# STM32.net
KiCad netlist of a schematic drawn in Altium Designer
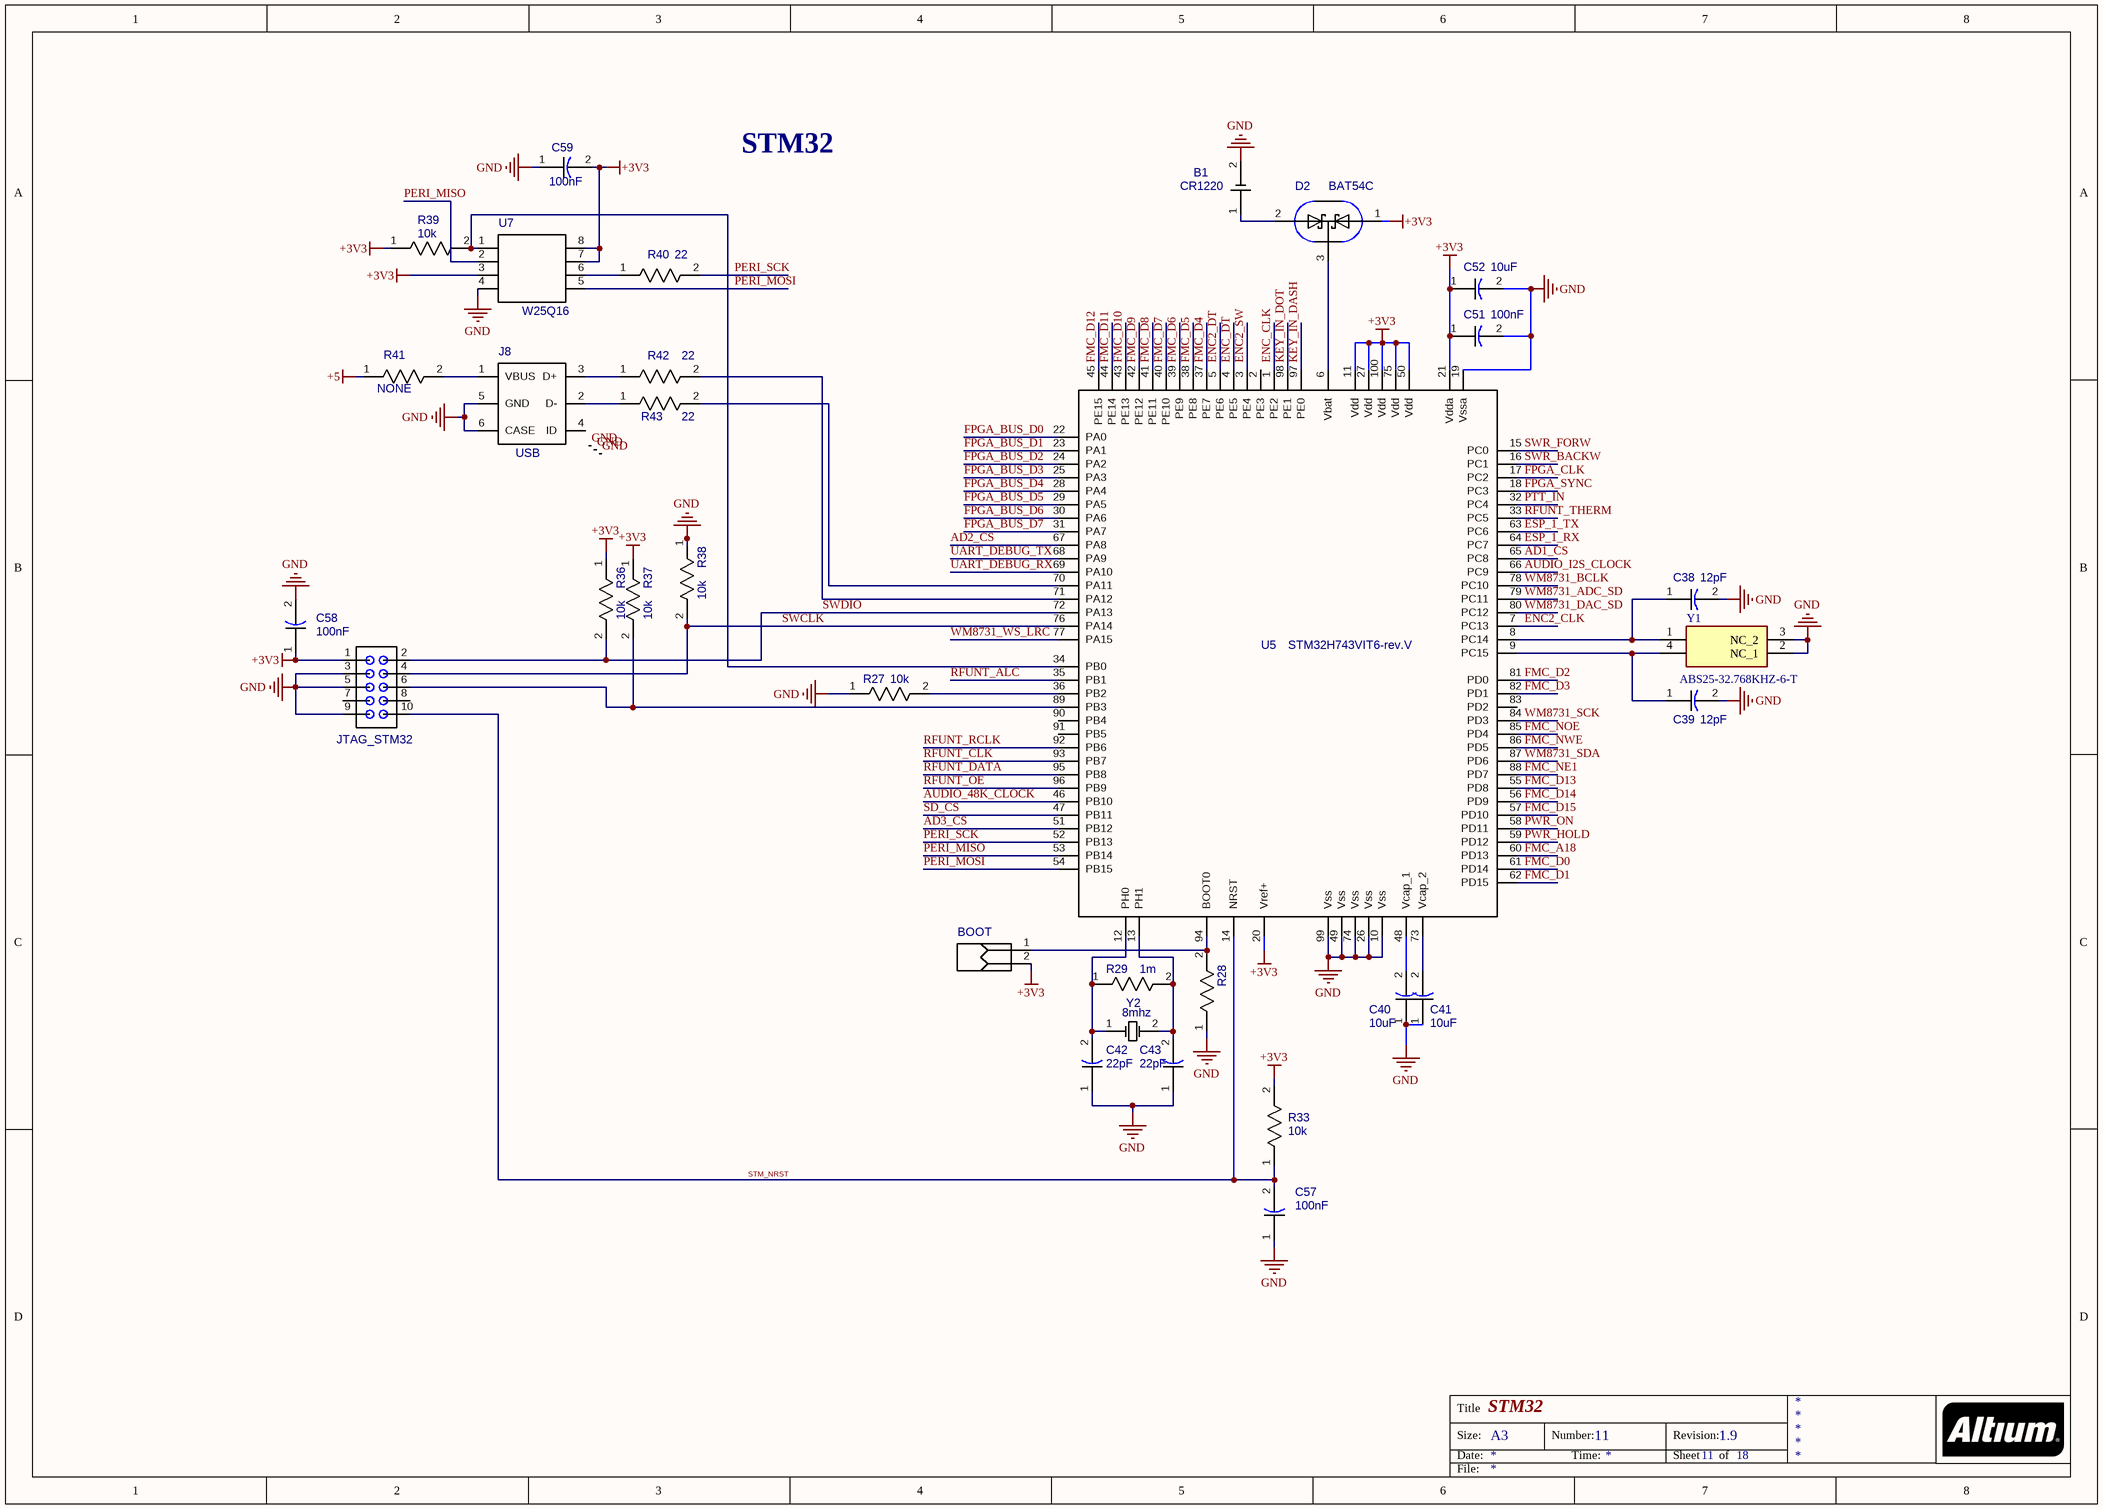
[diagram p0: STM32.SchDoc]

(export (version "E")
  (design (tool "Eeschema 10.0.6"))
  (components
    (comp (ref "B1")
      (value "CR1220")
      (footprint "BR1632A/FA")
      (description "BR1632A/FA")
      (libsource (lib "*") (part "BR1632A/FA"))
    )
    (comp (ref "BOOT")
      (value "~")
      (footprint "51022-0200")
      (description "2 Pin")
      (libsource (lib "*") (part "51022-0200"))
    )
    (comp (ref "C38")
      (value "12pF")
      (footprint "CAP_0805")
      (description "CAP_0805")
      (libsource (lib "*") (part "CAP_0805"))
    )
    (comp (ref "C39")
      (value "12pF")
      (footprint "CAP_0805")
      (description "CAP_0805")
      (libsource (lib "*") (part "CAP_0805"))
    )
    (comp (ref "C40")
      (value "10uF")
      (footprint "CAP_0805")
      (description "CAP_0805")
      (libsource (lib "*") (part "CAP_0805"))
    )
    (comp (ref "C41")
      (value "10uF")
      (footprint "CAP_0805")
      (description "CAP_0805")
      (libsource (lib "*") (part "CAP_0805"))
    )
    (comp (ref "C42")
      (value "22pF")
      (footprint "CAP_0805")
      (description "CAP_0805")
      (libsource (lib "*") (part "CAP_0805"))
    )
    (comp (ref "C43")
      (value "22pF")
      (footprint "CAP_0805")
      (description "CAP_0805")
      (libsource (lib "*") (part "CAP_0805"))
    )
    (comp (ref "C51")
      (value "100nF")
      (footprint "CAP_0805")
      (description "CAP_0805")
      (libsource (lib "*") (part "CAP_0805"))
    )
    (comp (ref "C52")
      (value "10uF")
      (footprint "CAP_0805")
      (description "CAP_0805")
      (libsource (lib "*") (part "CAP_0805"))
    )
    (comp (ref "C57")
      (value "100nF")
      (footprint "CAP_0805")
      (description "CAP_0805")
      (libsource (lib "*") (part "CAP_0805"))
    )
    (comp (ref "C58")
      (value "100nF")
      (footprint "CAP_0805")
      (description "CAP_0805")
      (libsource (lib "*") (part "CAP_0805"))
    )
    (comp (ref "C59")
      (value "100nF")
      (footprint "CAP_0805")
      (description "CAP_0805")
      (libsource (lib "*") (part "CAP_0805"))
    )
    (comp (ref "D2") (value "BAT54C") (footprint "BAT54C") (libsource (lib "*") (part "BAT54C")))
    (comp (ref "J8")
      (value "USB")
      (footprint "2-1734035-3")
      (description "2-1734035-3")
      (libsource (lib "*") (part "2-1734035-3"))
    )
    (comp (ref "JTAG_STM32")
      (value "~")
      (footprint "IDC10")
      (description "2*5 Pin")
      (libsource (lib "*") (part "IDC10"))
    )
    (comp (ref "R27")
      (value "10k")
      (footprint "RES_0805")
      (description "RES_0805")
      (libsource (lib "*") (part "RES_0805"))
    )
    (comp (ref "R28")
      (value "10k")
      (footprint "RES_0805")
      (description "RES_0805")
      (libsource (lib "*") (part "RES_0805"))
    )
    (comp (ref "R29")
      (value "1m")
      (footprint "RES_0805")
      (description "RES_0805")
      (libsource (lib "*") (part "RES_0805"))
    )
    (comp (ref "R33")
      (value "10k")
      (footprint "RES_0805")
      (description "RES_0805")
      (libsource (lib "*") (part "RES_0805"))
    )
    (comp (ref "R36")
      (value "10k")
      (footprint "RES_0805")
      (description "RES_0805")
      (libsource (lib "*") (part "RES_0805"))
    )
    (comp (ref "R37")
      (value "10k")
      (footprint "RES_0805")
      (description "RES_0805")
      (libsource (lib "*") (part "RES_0805"))
    )
    (comp (ref "R38")
      (value "10k")
      (footprint "RES_0805")
      (description "RES_0805")
      (libsource (lib "*") (part "RES_0805"))
    )
    (comp (ref "R39")
      (value "10k")
      (footprint "RES_0805")
      (description "RES_0805")
      (libsource (lib "*") (part "RES_0805"))
    )
    (comp (ref "R40")
      (value "22")
      (footprint "RES_0805")
      (description "RES_0805")
      (libsource (lib "*") (part "RES_0805"))
    )
    (comp (ref "R41")
      (value "NONE")
      (footprint "RES_0805")
      (description "RES_0805")
      (libsource (lib "*") (part "RES_0805"))
    )
    (comp (ref "R42")
      (value "22")
      (footprint "RES_0805")
      (description "RES_0805")
      (libsource (lib "*") (part "RES_0805"))
    )
    (comp (ref "R43")
      (value "22")
      (footprint "RES_0805")
      (description "RES_0805")
      (libsource (lib "*") (part "RES_0805"))
    )
    (comp (ref "U5")
      (value "STM32H743VIT6-rev.V")
      (footprint "STM32H743VIT6")
      (description "STM32H743VIT6")
      (libsource (lib "*") (part "STM32H743VIT6"))
    )
    (comp (ref "U7") (value "W25Q16") (footprint "W25Q16") (libsource (lib "*") (part "W25Q16")))
    (comp (ref "Y1")
      (value "ABS25-32.768KHZ-6-T")
      (footprint "SamacSys:ABS25")
      (description "Crystal or Oscillator")
      (fields
        (field (name "MOUSER PART NUMBER") "815-ABS25-32.768K6-T")
        (field (name "RS PART NUMBER") "1712795P")
      )
      (libsource (lib "*") (part "ABS25-32.768KHZ-6-T"))
    )
    (comp (ref "Y2")
      (value "8mhz")
      (footprint "ECS-200-20-1")
      (description "ECS-200-20-1")
      (libsource (lib "*") (part "ECS-200-20-1"))
    )
  )
  (nets
    (net (code "1") (name "+3V3") (class "Default")
      (node (ref "BOOT") (pin "2") (pinfunction "2_2") (pintype "passive"))
      (node (ref "C51") (pin "1") (pinfunction "1_1") (pintype "passive"))
      (node (ref "C52") (pin "1") (pinfunction "1_1") (pintype "passive"))
      (node (ref "C58") (pin "1") (pinfunction "1_1") (pintype "passive"))
      (node (ref "C59") (pin "2") (pinfunction "2_2") (pintype "passive"))
      (node (ref "D2") (pin "1") (pinfunction "(A1)_1") (pintype "passive"))
      (node (ref "JTAG_STM32") (pin "1") (pinfunction "1_1") (pintype "passive"))
      (node (ref "R33") (pin "2") (pinfunction "2_2") (pintype "passive"))
      (node (ref "R36") (pin "1") (pinfunction "1_1") (pintype "passive"))
      (node (ref "R37") (pin "1") (pinfunction "1_1") (pintype "passive"))
      (node (ref "R39") (pin "1") (pinfunction "1_1") (pintype "passive"))
      (node (ref "U5") (pin "100") (pinfunction "Vdd_100") (pintype "passive"))
      (node (ref "U5") (pin "11") (pinfunction "Vdd_11") (pintype "passive"))
      (node (ref "U5") (pin "20") (pinfunction "Vref+_20") (pintype "passive"))
      (node (ref "U5") (pin "21") (pinfunction "Vdda_21") (pintype "passive"))
      (node (ref "U5") (pin "27") (pinfunction "Vdd_27") (pintype "passive"))
      (node (ref "U5") (pin "50") (pinfunction "Vdd_50") (pintype "passive"))
      (node (ref "U5") (pin "75") (pinfunction "Vdd_75") (pintype "passive"))
      (node (ref "U7") (pin "3") (pinfunction "WP_3") (pintype "passive"))
      (node (ref "U7") (pin "7") (pinfunction "HOLD_7") (pintype "passive"))
      (node (ref "U7") (pin "8") (pinfunction "VCC_8") (pintype "passive"))
    )
    (net (code "2") (name "+5") (class "Default")
      (node (ref "R41") (pin "1") (pinfunction "1_1") (pintype "passive"))
    )
    (net (code "3") (name "/AD1_CS") (class "Default")
      (node (ref "U5") (pin "65") (pinfunction "PC8_65") (pintype "passive"))
    )
    (net (code "4") (name "/AD2_CS") (class "Default")
      (node (ref "U5") (pin "67") (pinfunction "PA8_67") (pintype "passive"))
    )
    (net (code "5") (name "/AD3_CS") (class "Default")
      (node (ref "U5") (pin "51") (pinfunction "PB12_51") (pintype "passive"))
    )
    (net (code "6") (name "/AUDIO_48K_CLOCK") (class "Default")
      (node (ref "U5") (pin "46") (pinfunction "PB10_46") (pintype "passive"))
    )
    (net (code "7") (name "/AUDIO_I2S_CLOCK") (class "Default")
      (node (ref "U5") (pin "66") (pinfunction "PC9_66") (pintype "passive"))
    )
    (net (code "8") (name "/ENC2_CLK") (class "Default")
      (node (ref "U5") (pin "7") (pinfunction "PC13_7") (pintype "passive"))
    )
    (net (code "9") (name "/ENC2_DT") (class "Default")
      (node (ref "U5") (pin "5") (pinfunction "PE6_5") (pintype "passive"))
    )
    (net (code "10") (name "/ENC2_SW") (class "Default")
      (node (ref "U5") (pin "3") (pinfunction "PE4_3") (pintype "passive"))
    )
    (net (code "11") (name "/ENC_CLK") (class "Default")
      (node (ref "U5") (pin "1") (pinfunction "PE2_1") (pintype "passive"))
    )
    (net (code "12") (name "/ENC_DT") (class "Default")
      (node (ref "U5") (pin "4") (pinfunction "PE5_4") (pintype "passive"))
    )
    (net (code "13") (name "/ESP_1_RX") (class "Default")
      (node (ref "U5") (pin "64") (pinfunction "PC7_64") (pintype "passive"))
    )
    (net (code "14") (name "/ESP_1_TX") (class "Default")
      (node (ref "U5") (pin "63") (pinfunction "PC6_63") (pintype "passive"))
    )
    (net (code "15") (name "/FMC_A18") (class "Default")
      (node (ref "U5") (pin "60") (pinfunction "PD13_60") (pintype "passive"))
    )
    (net (code "16") (name "/FMC_D0") (class "Default")
      (node (ref "U5") (pin "61") (pinfunction "PD14_61") (pintype "passive"))
    )
    (net (code "17") (name "/FMC_D1") (class "Default")
      (node (ref "U5") (pin "62") (pinfunction "PD15_62") (pintype "passive"))
    )
    (net (code "18") (name "/FMC_D2") (class "Default")
      (node (ref "U5") (pin "81") (pinfunction "PD0_81") (pintype "passive"))
    )
    (net (code "19") (name "/FMC_D3") (class "Default")
      (node (ref "U5") (pin "82") (pinfunction "PD1_82") (pintype "passive"))
    )
    (net (code "20") (name "/FMC_D4") (class "Default")
      (node (ref "U5") (pin "37") (pinfunction "PE7_37") (pintype "passive"))
    )
    (net (code "21") (name "/FMC_D5") (class "Default")
      (node (ref "U5") (pin "38") (pinfunction "PE8_38") (pintype "passive"))
    )
    (net (code "22") (name "/FMC_D6") (class "Default")
      (node (ref "U5") (pin "39") (pinfunction "PE9_39") (pintype "passive"))
    )
    (net (code "23") (name "/FMC_D7") (class "Default")
      (node (ref "U5") (pin "40") (pinfunction "PE10_40") (pintype "passive"))
    )
    (net (code "24") (name "/FMC_D8") (class "Default")
      (node (ref "U5") (pin "41") (pinfunction "PE11_41") (pintype "passive"))
    )
    (net (code "25") (name "/FMC_D9") (class "Default")
      (node (ref "U5") (pin "42") (pinfunction "PE12_42") (pintype "passive"))
    )
    (net (code "26") (name "/FMC_D10") (class "Default")
      (node (ref "U5") (pin "43") (pinfunction "PE13_43") (pintype "passive"))
    )
    (net (code "27") (name "/FMC_D11") (class "Default")
      (node (ref "U5") (pin "44") (pinfunction "PE14_44") (pintype "passive"))
    )
    (net (code "28") (name "/FMC_D12") (class "Default")
      (node (ref "U5") (pin "45") (pinfunction "PE15_45") (pintype "passive"))
    )
    (net (code "29") (name "/FMC_D13") (class "Default")
      (node (ref "U5") (pin "55") (pinfunction "PD8_55") (pintype "passive"))
    )
    (net (code "30") (name "/FMC_D14") (class "Default")
      (node (ref "U5") (pin "56") (pinfunction "PD9_56") (pintype "passive"))
    )
    (net (code "31") (name "/FMC_D15") (class "Default")
      (node (ref "U5") (pin "57") (pinfunction "PD10_57") (pintype "passive"))
    )
    (net (code "32") (name "/FMC_NE1") (class "Default")
      (node (ref "U5") (pin "88") (pinfunction "PD7_88") (pintype "passive"))
    )
    (net (code "33") (name "/FMC_NOE") (class "Default")
      (node (ref "U5") (pin "85") (pinfunction "PD4_85") (pintype "passive"))
    )
    (net (code "34") (name "/FMC_NWE") (class "Default")
      (node (ref "U5") (pin "86") (pinfunction "PD5_86") (pintype "passive"))
    )
    (net (code "35") (name "/FPGA_BUS_D0") (class "Default")
      (node (ref "U5") (pin "22") (pinfunction "PA0_22") (pintype "passive"))
    )
    (net (code "36") (name "/FPGA_BUS_D1") (class "Default")
      (node (ref "U5") (pin "23") (pinfunction "PA1_23") (pintype "passive"))
    )
    (net (code "37") (name "/FPGA_BUS_D2") (class "Default")
      (node (ref "U5") (pin "24") (pinfunction "PA2_24") (pintype "passive"))
    )
    (net (code "38") (name "/FPGA_BUS_D3") (class "Default")
      (node (ref "U5") (pin "25") (pinfunction "PA3_25") (pintype "passive"))
    )
    (net (code "39") (name "/FPGA_BUS_D4") (class "Default")
      (node (ref "U5") (pin "28") (pinfunction "PA4_28") (pintype "passive"))
    )
    (net (code "40") (name "/FPGA_BUS_D5") (class "Default")
      (node (ref "U5") (pin "29") (pinfunction "PA5_29") (pintype "passive"))
    )
    (net (code "41") (name "/FPGA_BUS_D6") (class "Default")
      (node (ref "U5") (pin "30") (pinfunction "PA6_30") (pintype "passive"))
    )
    (net (code "42") (name "/FPGA_BUS_D7") (class "Default")
      (node (ref "U5") (pin "31") (pinfunction "PA7_31") (pintype "passive"))
    )
    (net (code "43") (name "/FPGA_CLK") (class "Default")
      (node (ref "U5") (pin "17") (pinfunction "PC2_17") (pintype "passive"))
    )
    (net (code "44") (name "/FPGA_SYNC") (class "Default")
      (node (ref "U5") (pin "18") (pinfunction "PC3_18") (pintype "passive"))
    )
    (net (code "45") (name "/KEY_IN_DASH") (class "Default")
      (node (ref "U5") (pin "97") (pinfunction "PE0_97") (pintype "passive"))
    )
    (net (code "46") (name "/KEY_IN_DOT") (class "Default")
      (node (ref "U5") (pin "98") (pinfunction "PE1_98") (pintype "passive"))
    )
    (net (code "47") (name "/PERI_MISO") (class "Default")
      (node (ref "U5") (pin "53") (pinfunction "PB14_53") (pintype "passive"))
      (node (ref "U7") (pin "2") (pinfunction "SO_2") (pintype "passive"))
    )
    (net (code "48") (name "/PERI_MOSI") (class "Default")
      (node (ref "U5") (pin "54") (pinfunction "PB15_54") (pintype "passive"))
      (node (ref "U7") (pin "5") (pinfunction "SI_5") (pintype "passive"))
    )
    (net (code "49") (name "/PERI_SCK") (class "Default")
      (node (ref "R40") (pin "2") (pinfunction "2_2") (pintype "passive"))
      (node (ref "U5") (pin "52") (pinfunction "PB13_52") (pintype "passive"))
    )
    (net (code "50") (name "/PTT_IN") (class "Default")
      (node (ref "U5") (pin "32") (pinfunction "PC4_32") (pintype "passive"))
    )
    (net (code "51") (name "/PWR_HOLD") (class "Default")
      (node (ref "U5") (pin "59") (pinfunction "PD12_59") (pintype "passive"))
    )
    (net (code "52") (name "/PWR_ON") (class "Default")
      (node (ref "U5") (pin "58") (pinfunction "PD11_58") (pintype "passive"))
    )
    (net (code "53") (name "/RFUNT_ALC") (class "Default")
      (node (ref "U5") (pin "35") (pinfunction "PB1_35") (pintype "passive"))
    )
    (net (code "54") (name "/RFUNT_CLK") (class "Default")
      (node (ref "U5") (pin "93") (pinfunction "PB7_93") (pintype "passive"))
    )
    (net (code "55") (name "/RFUNT_DATA") (class "Default")
      (node (ref "U5") (pin "95") (pinfunction "PB8_95") (pintype "passive"))
    )
    (net (code "56") (name "/RFUNT_OE") (class "Default")
      (node (ref "U5") (pin "96") (pinfunction "PB9_96") (pintype "passive"))
    )
    (net (code "57") (name "/RFUNT_RCLK") (class "Default")
      (node (ref "U5") (pin "92") (pinfunction "PB6_92") (pintype "passive"))
    )
    (net (code "58") (name "/RFUNT_THERM") (class "Default")
      (node (ref "U5") (pin "33") (pinfunction "PC5_33") (pintype "passive"))
    )
    (net (code "59") (name "/SD_CS") (class "Default")
      (node (ref "U5") (pin "47") (pinfunction "PB11_47") (pintype "passive"))
    )
    (net (code "60") (name "/STM_NRST") (class "Default")
      (node (ref "C57") (pin "2") (pinfunction "2_2") (pintype "passive"))
      (node (ref "JTAG_STM32") (pin "10") (pinfunction "10_10") (pintype "passive"))
      (node (ref "R33") (pin "1") (pinfunction "1_1") (pintype "passive"))
      (node (ref "U5") (pin "14") (pinfunction "NRST_14") (pintype "passive"))
    )
    (net (code "61") (name "/SWCLK") (class "Default")
      (node (ref "JTAG_STM32") (pin "4") (pinfunction "4_4") (pintype "passive"))
      (node (ref "R38") (pin "2") (pinfunction "2_2") (pintype "passive"))
      (node (ref "U5") (pin "76") (pinfunction "PA14_76") (pintype "passive"))
    )
    (net (code "62") (name "/SWDIO") (class "Default")
      (node (ref "JTAG_STM32") (pin "2") (pinfunction "2_2") (pintype "passive"))
      (node (ref "R36") (pin "2") (pinfunction "2_2") (pintype "passive"))
      (node (ref "U5") (pin "72") (pinfunction "PA13_72") (pintype "passive"))
    )
    (net (code "63") (name "/SWR_BACKW") (class "Default")
      (node (ref "U5") (pin "16") (pinfunction "PC1_16") (pintype "passive"))
    )
    (net (code "64") (name "/SWR_FORW") (class "Default")
      (node (ref "U5") (pin "15") (pinfunction "PC0_15") (pintype "passive"))
    )
    (net (code "65") (name "/UART_DEBUG_RX") (class "Default")
      (node (ref "U5") (pin "69") (pinfunction "PA10_69") (pintype "passive"))
    )
    (net (code "66") (name "/UART_DEBUG_TX") (class "Default")
      (node (ref "U5") (pin "68") (pinfunction "PA9_68") (pintype "passive"))
    )
    (net (code "67") (name "/WM8731_ADC_SD") (class "Default")
      (node (ref "U5") (pin "79") (pinfunction "PC11_79") (pintype "passive"))
    )
    (net (code "68") (name "/WM8731_BCLK") (class "Default")
      (node (ref "U5") (pin "78") (pinfunction "PC10_78") (pintype "passive"))
    )
    (net (code "69") (name "/WM8731_DAC_SD") (class "Default")
      (node (ref "U5") (pin "80") (pinfunction "PC12_80") (pintype "passive"))
    )
    (net (code "70") (name "/WM8731_SCK") (class "Default")
      (node (ref "U5") (pin "84") (pinfunction "PD3_84") (pintype "passive"))
    )
    (net (code "71") (name "/WM8731_SDA") (class "Default")
      (node (ref "U5") (pin "87") (pinfunction "PD6_87") (pintype "passive"))
    )
    (net (code "72") (name "/WM8731_WS_LRC") (class "Default")
      (node (ref "U5") (pin "77") (pinfunction "PA15_77") (pintype "passive"))
    )
    (net (code "73") (name "GND") (class "Default")
      (node (ref "B1") (pin "2") (pinfunction "NEG_2") (pintype "passive"))
      (node (ref "C38") (pin "2") (pinfunction "2_2") (pintype "passive"))
      (node (ref "C39") (pin "2") (pinfunction "2_2") (pintype "passive"))
      (node (ref "C40") (pin "1") (pinfunction "1_1") (pintype "passive"))
      (node (ref "C41") (pin "1") (pinfunction "1_1") (pintype "passive"))
      (node (ref "C42") (pin "1") (pinfunction "1_1") (pintype "passive"))
      (node (ref "C43") (pin "1") (pinfunction "1_1") (pintype "passive"))
      (node (ref "C51") (pin "2") (pinfunction "2_2") (pintype "passive"))
      (node (ref "C52") (pin "2") (pinfunction "2_2") (pintype "passive"))
      (node (ref "C57") (pin "1") (pinfunction "1_1") (pintype "passive"))
      (node (ref "C58") (pin "2") (pinfunction "2_2") (pintype "passive"))
      (node (ref "C59") (pin "1") (pinfunction "1_1") (pintype "passive"))
      (node (ref "J8") (pin "5") (pinfunction "GND_5") (pintype "passive"))
      (node (ref "J8") (pin "6") (pinfunction "CASE_6") (pintype "passive"))
      (node (ref "J8") (pin "7") (pinfunction "0_7") (pintype "passive"))
      (node (ref "J8") (pin "8") (pinfunction "0_8") (pintype "passive"))
      (node (ref "J8") (pin "9") (pinfunction "0_9") (pintype "passive"))
      (node (ref "JTAG_STM32") (pin "3") (pinfunction "3_3") (pintype "passive"))
      (node (ref "JTAG_STM32") (pin "5") (pinfunction "5_5") (pintype "passive"))
      (node (ref "JTAG_STM32") (pin "9") (pinfunction "9_9") (pintype "passive"))
      (node (ref "R27") (pin "1") (pinfunction "1_1") (pintype "passive"))
      (node (ref "R28") (pin "1") (pinfunction "1_1") (pintype "passive"))
      (node (ref "R38") (pin "1") (pinfunction "1_1") (pintype "passive"))
      (node (ref "U5") (pin "10") (pinfunction "Vss_10") (pintype "passive"))
      (node (ref "U5") (pin "19") (pinfunction "Vssa_19") (pintype "passive"))
      (node (ref "U5") (pin "26") (pinfunction "Vss_26") (pintype "passive"))
      (node (ref "U5") (pin "49") (pinfunction "Vss_49") (pintype "passive"))
      (node (ref "U5") (pin "74") (pinfunction "Vss_74") (pintype "passive"))
      (node (ref "U5") (pin "99") (pinfunction "Vss_99") (pintype "passive"))
      (node (ref "U7") (pin "4") (pinfunction "GND_4") (pintype "passive"))
      (node (ref "Y1") (pin "2") (pinfunction "NC_1_2") (pintype "passive"))
      (node (ref "Y1") (pin "3") (pinfunction "NC_2_3") (pintype "passive"))
    )
    (net (code "74") (name "Net-(B1-POS)") (class "Default")
      (node (ref "B1") (pin "1") (pinfunction "POS_1") (pintype "passive"))
      (node (ref "D2") (pin "2") (pinfunction "(A2)_2") (pintype "passive"))
    )
    (net (code "75") (name "Net-(D2-(K1),(K2))") (class "Default")
      (node (ref "D2") (pin "3") (pinfunction "(K1),(K2)_3") (pintype "passive"))
      (node (ref "U5") (pin "6") (pinfunction "Vbat_6") (pintype "passive"))
    )
    (net (code "76") (name "Net-(J8-D+)") (class "Default")
      (node (ref "J8") (pin "3") (pinfunction "D+_3") (pintype "passive"))
      (node (ref "R42") (pin "1") (pinfunction "1_1") (pintype "passive"))
    )
    (net (code "77") (name "Net-(J8-D-)") (class "Default")
      (node (ref "J8") (pin "2") (pinfunction "D-_2") (pintype "passive"))
      (node (ref "R43") (pin "1") (pinfunction "1_1") (pintype "passive"))
    )
    (net (code "78") (name "Net-(J8-VBUS)") (class "Default")
      (node (ref "J8") (pin "1") (pinfunction "VBUS_1") (pintype "passive"))
      (node (ref "R41") (pin "2") (pinfunction "2_2") (pintype "passive"))
    )
    (net (code "79") (name "Net-(U5-BOOT0)") (class "Default")
      (node (ref "BOOT") (pin "1") (pinfunction "1_1") (pintype "passive"))
      (node (ref "R28") (pin "2") (pinfunction "2_2") (pintype "passive"))
      (node (ref "U5") (pin "94") (pinfunction "BOOT0_94") (pintype "passive"))
    )
    (net (code "80") (name "Net-(U5-PA11)") (class "Default")
      (node (ref "R43") (pin "2") (pinfunction "2_2") (pintype "passive"))
      (node (ref "U5") (pin "70") (pinfunction "PA11_70") (pintype "passive"))
    )
    (net (code "81") (name "Net-(U5-PA12)") (class "Default")
      (node (ref "R42") (pin "2") (pinfunction "2_2") (pintype "passive"))
      (node (ref "U5") (pin "71") (pinfunction "PA12_71") (pintype "passive"))
    )
    (net (code "82") (name "Net-(U5-PB0)") (class "Default")
      (node (ref "R39") (pin "2") (pinfunction "2_2") (pintype "passive"))
      (node (ref "U5") (pin "34") (pinfunction "PB0_34") (pintype "passive"))
      (node (ref "U7") (pin "1") (pinfunction "CS_1") (pintype "passive"))
    )
    (net (code "83") (name "Net-(U5-PB2)") (class "Default")
      (node (ref "R27") (pin "2") (pinfunction "2_2") (pintype "passive"))
      (node (ref "U5") (pin "36") (pinfunction "PB2_36") (pintype "passive"))
    )
    (net (code "84") (name "Net-(U5-PB3)") (class "Default")
      (node (ref "JTAG_STM32") (pin "6") (pinfunction "6_6") (pintype "passive"))
      (node (ref "R37") (pin "2") (pinfunction "2_2") (pintype "passive"))
      (node (ref "U5") (pin "89") (pinfunction "PB3_89") (pintype "passive"))
    )
    (net (code "85") (name "Net-(U5-PC14)") (class "Default")
      (node (ref "C38") (pin "1") (pinfunction "1_1") (pintype "passive"))
      (node (ref "U5") (pin "8") (pinfunction "PC14_8") (pintype "passive"))
      (node (ref "Y1") (pin "1") (pinfunction "1_1") (pintype "passive"))
    )
    (net (code "86") (name "Net-(U5-PC15)") (class "Default")
      (node (ref "C39") (pin "1") (pinfunction "1_1") (pintype "passive"))
      (node (ref "U5") (pin "9") (pinfunction "PC15_9") (pintype "passive"))
      (node (ref "Y1") (pin "4") (pinfunction "4_4") (pintype "passive"))
    )
    (net (code "87") (name "Net-(U5-PH0)") (class "Default")
      (node (ref "C42") (pin "2") (pinfunction "2_2") (pintype "passive"))
      (node (ref "R29") (pin "1") (pinfunction "1_1") (pintype "passive"))
      (node (ref "U5") (pin "12") (pinfunction "PH0_12") (pintype "passive"))
      (node (ref "Y2") (pin "1") (pinfunction "OSC1_1") (pintype "passive"))
    )
    (net (code "88") (name "Net-(U5-PH1)") (class "Default")
      (node (ref "C43") (pin "2") (pinfunction "2_2") (pintype "passive"))
      (node (ref "R29") (pin "2") (pinfunction "2_2") (pintype "passive"))
      (node (ref "U5") (pin "13") (pinfunction "PH1_13") (pintype "passive"))
      (node (ref "Y2") (pin "2") (pinfunction "OSC2_2") (pintype "passive"))
    )
    (net (code "89") (name "Net-(U5-Vcap_1)") (class "Default")
      (node (ref "C40") (pin "2") (pinfunction "2_2") (pintype "passive"))
      (node (ref "U5") (pin "48") (pinfunction "Vcap_1_48") (pintype "passive"))
    )
    (net (code "90") (name "Net-(U5-Vcap_2)") (class "Default")
      (node (ref "C41") (pin "2") (pinfunction "2_2") (pintype "passive"))
      (node (ref "U5") (pin "73") (pinfunction "Vcap_2_73") (pintype "passive"))
    )
    (net (code "91") (name "Net-(U7-CLK)") (class "Default")
      (node (ref "R40") (pin "1") (pinfunction "1_1") (pintype "passive"))
      (node (ref "U7") (pin "6") (pinfunction "CLK_6") (pintype "passive"))
    )
    (net (code "92") (name "unconnected-(J8-ID-Pad4)") (class "Default")
      (node (ref "J8") (pin "4") (pinfunction "ID_4") (pintype "passive"))
    )
    (net (code "93") (name "unconnected-(JTAG_STM32-Pad7)") (class "Default")
      (node (ref "JTAG_STM32") (pin "7") (pinfunction "7_7") (pintype "passive"))
    )
    (net (code "94") (name "unconnected-(JTAG_STM32-Pad8)") (class "Default")
      (node (ref "JTAG_STM32") (pin "8") (pinfunction "8_8") (pintype "passive"))
    )
    (net (code "95") (name "unconnected-(U5-PB4-Pad90)") (class "Default")
      (node (ref "U5") (pin "90") (pinfunction "PB4_90") (pintype "passive"))
    )
    (net (code "96") (name "unconnected-(U5-PB5-Pad91)") (class "Default")
      (node (ref "U5") (pin "91") (pinfunction "PB5_91") (pintype "passive"))
    )
    (net (code "97") (name "unconnected-(U5-PD2-Pad83)") (class "Default")
      (node (ref "U5") (pin "83") (pinfunction "PD2_83") (pintype "passive"))
    )
    (net (code "98") (name "unconnected-(U5-PE3-Pad2)") (class "Default")
      (node (ref "U5") (pin "2") (pinfunction "PE3_2") (pintype "passive"))
    )
  )
)
